# ft231x-usbA.net
KiCad netlist of a schematic drawn in EAGLE
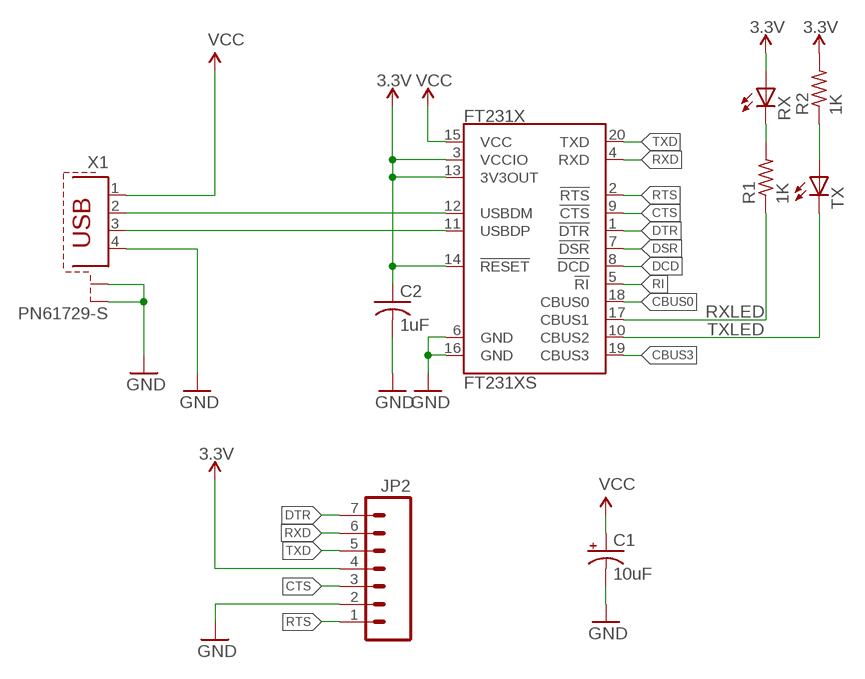
[diagram p0: schematic, sheet 1]

(export (version "E")
  (design (tool "Eeschema 10.0.6"))
  (components
    (comp (ref "C1")
      (value "10uF")
      (footprint "eagle-import:EIA3216")
      (libsource (lib "eagle-import") (part "CAP_POL1206"))
    )
    (comp (ref "C2")
      (value "1uF")
      (footprint "eagle-import:C0805")
      (libsource (lib "eagle-import") (part "C-USC0805"))
    )
    (comp (ref "FT231X")
      (value "FT231XS")
      (footprint "eagle-import:SSOP20_L")
      (libsource (lib "eagle-import") (part "FT231XS"))
    )
    (comp (ref "JP2")
      (value "M07")
      (footprint "eagle-import:1X07")
      (libsource (lib "eagle-import") (part "M07"))
    )
    (comp (ref "R1")
      (value "1K")
      (footprint "eagle-import:R0603")
      (libsource (lib "eagle-import") (part "R-US_R0603"))
    )
    (comp (ref "R2")
      (value "1K")
      (footprint "eagle-import:R0603")
      (libsource (lib "eagle-import") (part "R-US_R0603"))
    )
    (comp (ref "RX")
      (value "LEDCHIP-LED0805")
      (footprint "eagle-import:CHIP-LED0805")
      (libsource (lib "eagle-import") (part "LEDCHIP-LED0805"))
    )
    (comp (ref "TX")
      (value "LEDCHIP-LED0805")
      (footprint "eagle-import:CHIP-LED0805")
      (libsource (lib "eagle-import") (part "LEDCHIP-LED0805"))
    )
    (comp (ref "X1")
      (value "PN61729-S")
      (footprint "eagle-import:PN61729-S")
      (libsource (lib "eagle-import") (part "PN61729-S"))
    )
  )
  (nets
    (net (code "1") (name "/RXLED") (class "Default")
      (node (ref "FT231X") (pin "17") (pinfunction "CBUS1_17") (pintype "bidirectional"))
      (node (ref "R1") (pin "1") (pinfunction "1_1") (pintype "passive"))
    )
    (net (code "2") (name "/TXLED") (class "Default")
      (node (ref "FT231X") (pin "10") (pinfunction "CBUS2_10") (pintype "bidirectional"))
      (node (ref "TX") (pin "C") (pinfunction "C_C") (pintype "passive"))
    )
    (net (code "3") (name "3.3V") (class "Default")
      (node (ref "C2") (pin "1") (pinfunction "1_1") (pintype "passive"))
      (node (ref "FT231X") (pin "13") (pinfunction "3V3OUT_13") (pintype "bidirectional"))
      (node (ref "FT231X") (pin "14") (pinfunction "~{RESET}_14") (pintype "bidirectional"))
      (node (ref "FT231X") (pin "3") (pinfunction "VCCIO_3") (pintype "bidirectional"))
      (node (ref "JP2") (pin "4") (pinfunction "4_4") (pintype "passive"))
      (node (ref "R2") (pin "2") (pinfunction "2_2") (pintype "passive"))
      (node (ref "RX") (pin "A") (pinfunction "A_A") (pintype "passive"))
    )
    (net (code "4") (name "CBUS0") (class "Default")
      (node (ref "FT231X") (pin "18") (pinfunction "CBUS0_18") (pintype "bidirectional"))
    )
    (net (code "5") (name "CBUS3") (class "Default")
      (node (ref "FT231X") (pin "19") (pinfunction "CBUS3_19") (pintype "bidirectional"))
    )
    (net (code "6") (name "CTS") (class "Default")
      (node (ref "FT231X") (pin "9") (pinfunction "~{CTS}_9") (pintype "bidirectional"))
      (node (ref "JP2") (pin "3") (pinfunction "3_3") (pintype "passive"))
    )
    (net (code "7") (name "DCD") (class "Default")
      (node (ref "FT231X") (pin "8") (pinfunction "~{DCD}_8") (pintype "bidirectional"))
    )
    (net (code "8") (name "DSR") (class "Default")
      (node (ref "FT231X") (pin "7") (pinfunction "~{DSR}_7") (pintype "bidirectional"))
    )
    (net (code "9") (name "DTR") (class "Default")
      (node (ref "FT231X") (pin "1") (pinfunction "~{DTR}_1") (pintype "bidirectional"))
      (node (ref "JP2") (pin "7") (pinfunction "7_7") (pintype "passive"))
    )
    (net (code "10") (name "GND") (class "Default")
      (node (ref "C1") (pin "C") (pinfunction "-_C") (pintype "passive"))
      (node (ref "C2") (pin "2") (pinfunction "2_2") (pintype "passive"))
      (node (ref "FT231X") (pin "16") (pinfunction "GND_16") (pintype "bidirectional"))
      (node (ref "FT231X") (pin "6") (pinfunction "GND_6") (pintype "bidirectional"))
      (node (ref "JP2") (pin "2") (pinfunction "2_2") (pintype "passive"))
      (node (ref "X1") (pin "4") (pinfunction "4_4") (pintype "passive"))
      (node (ref "X1") (pin "S1") (pinfunction "S1_S1") (pintype "passive"))
      (node (ref "X1") (pin "S2") (pinfunction "S2_S2") (pintype "passive"))
    )
    (net (code "11") (name "Net-(FT231X-USBDM)") (class "Default")
      (node (ref "FT231X") (pin "12") (pinfunction "USBDM_12") (pintype "bidirectional"))
      (node (ref "X1") (pin "2") (pinfunction "2_2") (pintype "passive"))
    )
    (net (code "12") (name "Net-(FT231X-USBDP)") (class "Default")
      (node (ref "FT231X") (pin "11") (pinfunction "USBDP_11") (pintype "bidirectional"))
      (node (ref "X1") (pin "3") (pinfunction "3_3") (pintype "passive"))
    )
    (net (code "13") (name "Net-(R1-Pad2)") (class "Default")
      (node (ref "R1") (pin "2") (pinfunction "2_2") (pintype "passive"))
      (node (ref "RX") (pin "C") (pinfunction "C_C") (pintype "passive"))
    )
    (net (code "14") (name "Net-(R2-Pad1)") (class "Default")
      (node (ref "R2") (pin "1") (pinfunction "1_1") (pintype "passive"))
      (node (ref "TX") (pin "A") (pinfunction "A_A") (pintype "passive"))
    )
    (net (code "15") (name "RI") (class "Default")
      (node (ref "FT231X") (pin "5") (pinfunction "~{RI}_5") (pintype "bidirectional"))
    )
    (net (code "16") (name "RTS") (class "Default")
      (node (ref "FT231X") (pin "2") (pinfunction "~{RTS}_2") (pintype "bidirectional"))
      (node (ref "JP2") (pin "1") (pinfunction "1_1") (pintype "passive"))
    )
    (net (code "17") (name "RXD") (class "Default")
      (node (ref "FT231X") (pin "4") (pinfunction "RXD_4") (pintype "bidirectional"))
      (node (ref "JP2") (pin "6") (pinfunction "6_6") (pintype "passive"))
    )
    (net (code "18") (name "TXD") (class "Default")
      (node (ref "FT231X") (pin "20") (pinfunction "TXD_20") (pintype "bidirectional"))
      (node (ref "JP2") (pin "5") (pinfunction "5_5") (pintype "passive"))
    )
    (net (code "19") (name "VCC") (class "Default")
      (node (ref "C1") (pin "A") (pinfunction "+_A") (pintype "passive"))
      (node (ref "FT231X") (pin "15") (pinfunction "VCC_15") (pintype "bidirectional"))
      (node (ref "X1") (pin "1") (pinfunction "1_1") (pintype "passive"))
    )
  )
)
